# bits.net
KiCad netlist of a schematic drawn in EAGLE
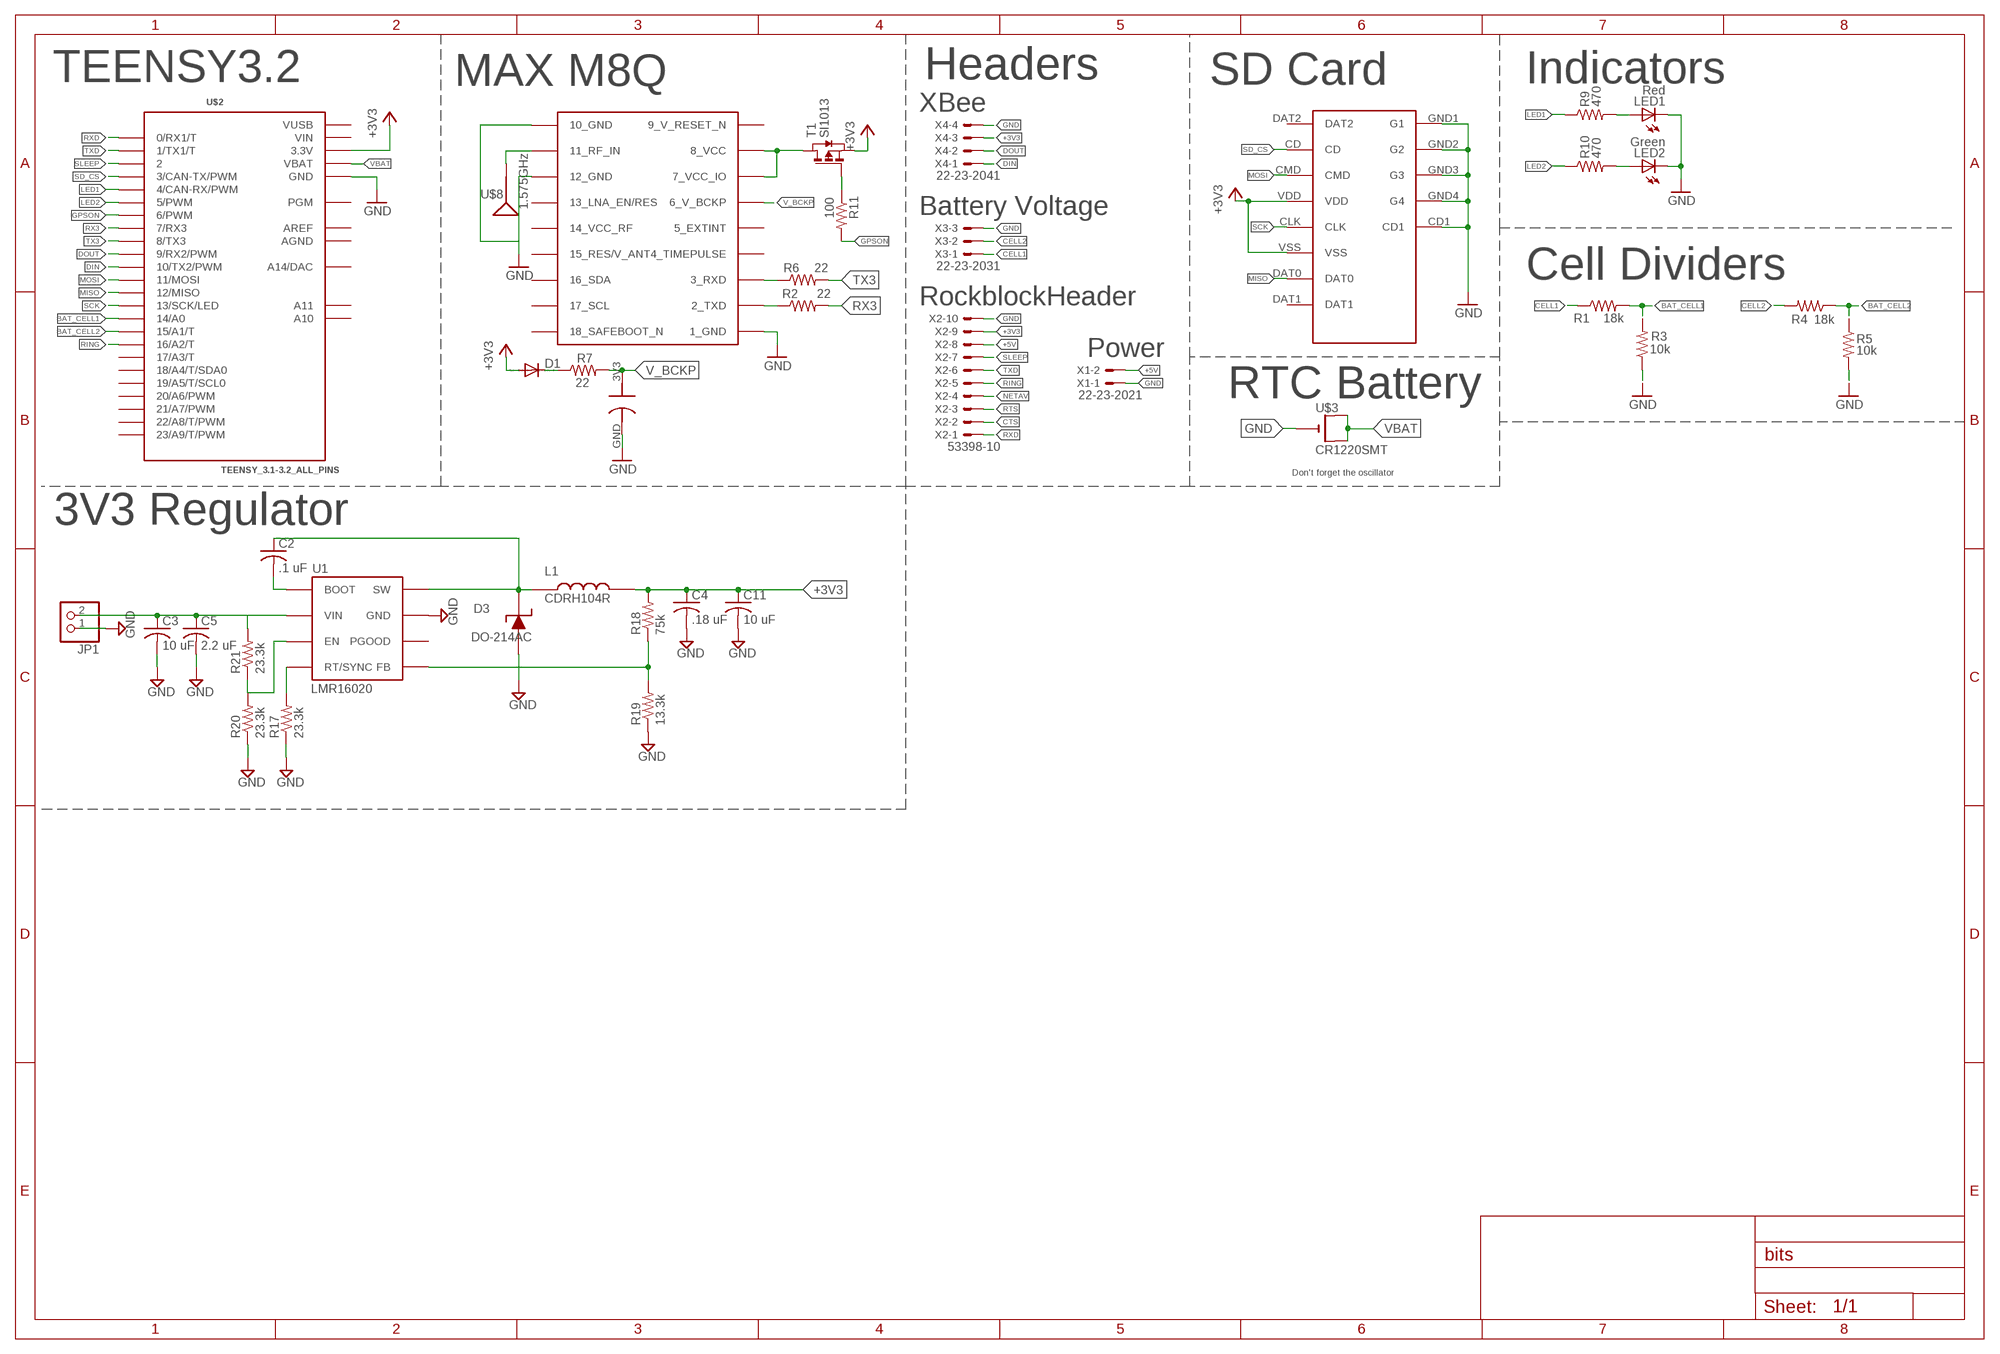
[diagram p0: schematic, sheet 1]

(export (version "E")
  (design (tool "Eeschema 10.0.6"))
  (components
    (comp (ref "C1")
      (value "DCK-3R3E204T614-E")
      (footprint "eagle-import:ELNASUPERCAP")
      (libsource (lib "eagle-import") (part "DCK-3R3E204T614-E"))
    )
    (comp (ref "C2")
      (value ".1 uF")
      (footprint "eagle-import:C0603")
      (libsource (lib "eagle-import") (part "C-USC0603"))
    )
    (comp (ref "C3")
      (value "10 uF")
      (footprint "eagle-import:C1210")
      (libsource (lib "eagle-import") (part "C-USC1210"))
    )
    (comp (ref "C4")
      (value ".18 uF")
      (footprint "eagle-import:C0603")
      (libsource (lib "eagle-import") (part "C-USC0603"))
    )
    (comp (ref "C5")
      (value "2.2 uF")
      (footprint "eagle-import:C1210")
      (libsource (lib "eagle-import") (part "C-USC1210"))
    )
    (comp (ref "C11")
      (value "10 uF")
      (footprint "eagle-import:C0603")
      (libsource (lib "eagle-import") (part "C-USC0603"))
    )
    (comp (ref "D1")
      (value "DIODE-SOD523")
      (footprint "eagle-import:SOD523")
      (libsource (lib "eagle-import") (part "DIODE-SOD523"))
    )
    (comp (ref "D3")
      (value "DO-214AC")
      (footprint "eagle-import:DO-214AC")
      (libsource (lib "eagle-import") (part "DO-214AC"))
    )
    (comp (ref "JP1")
      (value "PINHD-1X2")
      (footprint "eagle-import:1X02")
      (libsource (lib "eagle-import") (part "PINHD-1X2"))
    )
    (comp (ref "L1")
      (value "CDRH104R")
      (footprint "eagle-import:CDRH104R")
      (libsource (lib "eagle-import") (part "CDRH104R"))
    )
    (comp (ref "LED1")
      (value "Red")
      (footprint "eagle-import:CHIP-LED0603")
      (libsource (lib "eagle-import") (part "LEDCHIP-LED0603"))
    )
    (comp (ref "LED2")
      (value "Green")
      (footprint "eagle-import:CHIP-LED0603")
      (libsource (lib "eagle-import") (part "LEDCHIP-LED0603"))
    )
    (comp (ref "R1")
      (value "18k")
      (footprint "eagle-import:R0603")
      (libsource (lib "eagle-import") (part "resistor_R-US_R0603"))
    )
    (comp (ref "R2")
      (value "22")
      (footprint "eagle-import:R0603")
      (libsource (lib "eagle-import") (part "R-US_R0603"))
    )
    (comp (ref "R3")
      (value "10k")
      (footprint "eagle-import:R0603")
      (libsource (lib "eagle-import") (part "resistor_R-US_R0603"))
    )
    (comp (ref "R4")
      (value "18k")
      (footprint "eagle-import:R0603")
      (libsource (lib "eagle-import") (part "resistor_R-US_R0603"))
    )
    (comp (ref "R5")
      (value "10k")
      (footprint "eagle-import:R0603")
      (libsource (lib "eagle-import") (part "resistor_R-US_R0603"))
    )
    (comp (ref "R6")
      (value "22")
      (footprint "eagle-import:R0603")
      (libsource (lib "eagle-import") (part "R-US_R0603"))
    )
    (comp (ref "R7")
      (value "22")
      (footprint "eagle-import:R0603")
      (libsource (lib "eagle-import") (part "R-US_R0603"))
    )
    (comp (ref "R9")
      (value "470")
      (footprint "eagle-import:R0603")
      (libsource (lib "eagle-import") (part "resistor_R-US_R0603"))
    )
    (comp (ref "R10")
      (value "470")
      (footprint "eagle-import:R0603")
      (libsource (lib "eagle-import") (part "resistor_R-US_R0603"))
    )
    (comp (ref "R11")
      (value "100")
      (footprint "eagle-import:R0603")
      (libsource (lib "eagle-import") (part "R-US_R0603"))
    )
    (comp (ref "R17")
      (value "23.3k")
      (footprint "eagle-import:R0603")
      (libsource (lib "eagle-import") (part "resistor_R-US_R0603"))
    )
    (comp (ref "R18")
      (value "75k")
      (footprint "eagle-import:R0603")
      (libsource (lib "eagle-import") (part "resistor_R-US_R0603"))
    )
    (comp (ref "R19")
      (value "13.3k")
      (footprint "eagle-import:R0603")
      (libsource (lib "eagle-import") (part "resistor_R-US_R0603"))
    )
    (comp (ref "R20")
      (value "23.3k")
      (footprint "eagle-import:R0603")
      (libsource (lib "eagle-import") (part "resistor_R-US_R0603"))
    )
    (comp (ref "R21")
      (value "23.3k")
      (footprint "eagle-import:R0603")
      (libsource (lib "eagle-import") (part "resistor_R-US_R0603"))
    )
    (comp (ref "T1")
      (value "SI1013")
      (footprint "eagle-import:SC-75")
      (libsource (lib "eagle-import") (part "SI1013"))
    )
    (comp (ref "U$2")
      (value "TEENSY_3.1-3.2_ALL_PINS")
      (footprint "eagle-import:TEENSY_3.0-3.2&LC_ALL_PINS")
      (libsource (lib "eagle-import") (part "TEENSY_3.1-3.2_ALL_PINS"))
    )
    (comp (ref "U$3")
      (value "CR1220SMT")
      (footprint "eagle-import:CR1220-SMD")
      (libsource (lib "eagle-import") (part "CR1220SMT"))
    )
    (comp (ref "U$4")
      (value "MICRO_SD")
      (footprint "eagle-import:MICRO_SD_HINGED")
      (libsource (lib "eagle-import") (part "MICRO_SD"))
    )
    (comp (ref "U$7")
      (value "MAX-M8")
      (footprint "eagle-import:MAX-M8")
      (libsource (lib "eagle-import") (part "MAX-M8"))
    )
    (comp (ref "U$8")
      (value "1.575GHz")
      (footprint "eagle-import:SPARKFUN-GPS_ANT-GPS-2X7MM")
      (libsource (lib "eagle-import") (part "SPARKFUN-GPS_ANTENNAGPS-2X7MM"))
    )
    (comp (ref "U1")
      (value "LMR16020")
      (footprint "eagle-import:SO8")
      (libsource (lib "eagle-import") (part "LMR16020"))
    )
    (comp (ref "X1")
      (value "22-23-2021")
      (footprint "eagle-import:22-23-2021")
      (fields (field (name "MF") "MOLEX"))
      (libsource (lib "eagle-import") (part "22-23-2021"))
    )
    (comp (ref "X2")
      (value "53398-10")
      (footprint "eagle-import:53398-10")
      (fields (field (name "MF") "MOLEX") (field (name "MPN") "53398-1071"))
      (libsource (lib "eagle-import") (part "53?-10398"))
    )
    (comp (ref "X3")
      (value "22-23-2031")
      (footprint "eagle-import:22-23-2031")
      (fields (field (name "MF") "MOLEX"))
      (libsource (lib "eagle-import") (part "22-23-2031"))
    )
    (comp (ref "X4")
      (value "22-23-2041")
      (footprint "eagle-import:22-23-2041")
      (fields (field (name "MF") "MOLEX"))
      (libsource (lib "eagle-import") (part "22-23-2041"))
    )
  )
  (nets
    (net (code "1") (name "+3V3") (class "Default")
      (node (ref "C11") (pin "1") (pinfunction "1_1") (pintype "passive"))
      (node (ref "C4") (pin "1") (pinfunction "1_1") (pintype "passive"))
      (node (ref "D1") (pin "A") (pinfunction "A_A") (pintype "passive"))
      (node (ref "L1") (pin "P$2") (pinfunction "P$2_P$2") (pintype "bidirectional"))
      (node (ref "R18") (pin "2") (pinfunction "2_2") (pintype "passive"))
      (node (ref "T1") (pin "P$2") (pinfunction "S_P$2") (pintype "passive"))
      (node (ref "U$2") (pin "3.3V") (pinfunction "3.3V_3.3V") (pintype "power_in"))
      (node (ref "U$2") (pin "3.3V1") (pinfunction "3.3V_3.3V1") (pintype "power_in"))
      (node (ref "U$4") (pin "VDD") (pinfunction "VDD_VDD") (pintype "bidirectional"))
      (node (ref "U$4") (pin "VSS") (pinfunction "VSS_VSS") (pintype "bidirectional"))
      (node (ref "X2") (pin "9") (pinfunction "S_9") (pintype "passive"))
      (node (ref "X4") (pin "3") (pinfunction "S_3") (pintype "passive"))
    )
    (net (code "2") (name "+5V") (class "Default")
      (node (ref "X1") (pin "2") (pinfunction "S_2") (pintype "passive"))
      (node (ref "X2") (pin "8") (pinfunction "S_8") (pintype "passive"))
    )
    (net (code "3") (name "/9_V_RESET_N") (class "Default")
      (node (ref "U$7") (pin "9_RESET_N") (pinfunction "9_V_RESET_N_9_RESET_N") (pintype "power_in"))
    )
    (net (code "4") (name "/AGND") (class "Default")
      (node (ref "U$2") (pin "AGND") (pinfunction "AGND_AGND") (pintype "power_in"))
    )
    (net (code "5") (name "/AREF") (class "Default")
      (node (ref "U$2") (pin "AREF") (pinfunction "AREF_AREF") (pintype "power_in"))
    )
    (net (code "6") (name "/VIN") (class "Default")
      (node (ref "U$2") (pin "VIN") (pinfunction "VIN_VIN") (pintype "power_in"))
    )
    (net (code "7") (name "/VUSB") (class "Default")
      (node (ref "U$2") (pin "VUSB") (pinfunction "VUSB_VUSB") (pintype "power_in"))
    )
    (net (code "8") (name "BAT_CELL1") (class "Default")
      (node (ref "R1") (pin "2") (pinfunction "2_2") (pintype "passive"))
      (node (ref "R3") (pin "2") (pinfunction "2_2") (pintype "passive"))
      (node (ref "U$2") (pin "14/A0") (pinfunction "14/A0_14/A0") (pintype "bidirectional"))
    )
    (net (code "9") (name "BAT_CELL2") (class "Default")
      (node (ref "R4") (pin "1") (pinfunction "1_1") (pintype "passive"))
      (node (ref "R5") (pin "1") (pinfunction "1_1") (pintype "passive"))
      (node (ref "U$2") (pin "15/A1") (pinfunction "15/A1/T_15/A1") (pintype "bidirectional"))
    )
    (net (code "10") (name "CELL1") (class "Default")
      (node (ref "R1") (pin "1") (pinfunction "1_1") (pintype "passive"))
      (node (ref "X3") (pin "1") (pinfunction "S_1") (pintype "passive"))
    )
    (net (code "11") (name "CELL2") (class "Default")
      (node (ref "R4") (pin "2") (pinfunction "2_2") (pintype "passive"))
      (node (ref "X3") (pin "2") (pinfunction "S_2") (pintype "passive"))
    )
    (net (code "12") (name "CTS") (class "Default")
      (node (ref "X2") (pin "2") (pinfunction "S_2") (pintype "passive"))
    )
    (net (code "13") (name "DIN") (class "Default")
      (node (ref "U$2") (pin "10") (pinfunction "10/TX2/PWM_10") (pintype "bidirectional"))
      (node (ref "X4") (pin "1") (pinfunction "S_1") (pintype "passive"))
    )
    (net (code "14") (name "DOUT") (class "Default")
      (node (ref "U$2") (pin "9") (pinfunction "9/RX2/PWM_9") (pintype "bidirectional"))
      (node (ref "X4") (pin "2") (pinfunction "S_2") (pintype "passive"))
    )
    (net (code "15") (name "GND") (class "Default")
      (node (ref "C1") (pin "GND") (pinfunction "GND_GND") (pintype "bidirectional"))
      (node (ref "C11") (pin "2") (pinfunction "2_2") (pintype "passive"))
      (node (ref "C3") (pin "2") (pinfunction "2_2") (pintype "passive"))
      (node (ref "C4") (pin "2") (pinfunction "2_2") (pintype "passive"))
      (node (ref "C5") (pin "2") (pinfunction "2_2") (pintype "passive"))
      (node (ref "D3") (pin "P$1") (pinfunction "P$1_P$1") (pintype "bidirectional"))
      (node (ref "JP1") (pin "1") (pinfunction "1_1") (pintype "passive"))
      (node (ref "LED1") (pin "C") (pinfunction "C_C") (pintype "passive"))
      (node (ref "LED2") (pin "C") (pinfunction "C_C") (pintype "passive"))
      (node (ref "R17") (pin "1") (pinfunction "1_1") (pintype "passive"))
      (node (ref "R19") (pin "1") (pinfunction "1_1") (pintype "passive"))
      (node (ref "R20") (pin "1") (pinfunction "1_1") (pintype "passive"))
      (node (ref "R3") (pin "1") (pinfunction "1_1") (pintype "passive"))
      (node (ref "R5") (pin "2") (pinfunction "2_2") (pintype "passive"))
      (node (ref "U$2") (pin "GND") (pinfunction "GND_GND") (pintype "power_in"))
      (node (ref "U$2") (pin "GND1") (pinfunction "GND_GND1") (pintype "power_in"))
      (node (ref "U$3") (pin "-") (pinfunction "-_-") (pintype "passive"))
      (node (ref "U$4") (pin "CD1") (pinfunction "CD1_CD1") (pintype "bidirectional"))
      (node (ref "U$4") (pin "GND1") (pinfunction "G1_GND1") (pintype "bidirectional"))
      (node (ref "U$4") (pin "GND2") (pinfunction "G2_GND2") (pintype "bidirectional"))
      (node (ref "U$4") (pin "GND3") (pinfunction "G3_GND3") (pintype "bidirectional"))
      (node (ref "U$4") (pin "GND4") (pinfunction "G4_GND4") (pintype "bidirectional"))
      (node (ref "U$7") (pin "10_GND") (pinfunction "10_GND_10_GND") (pintype "power_in"))
      (node (ref "U$7") (pin "12_GND") (pinfunction "12_GND_12_GND") (pintype "power_in"))
      (node (ref "U$7") (pin "1_GND") (pinfunction "1_GND_1_GND") (pintype "power_in"))
      (node (ref "U1") (pin "P$7") (pinfunction "GND_P$7") (pintype "bidirectional"))
      (node (ref "U1") (pin "PAD") (pinfunction "GND_PAD") (pintype "bidirectional"))
      (node (ref "X1") (pin "1") (pinfunction "S_1") (pintype "passive"))
      (node (ref "X2") (pin "10") (pinfunction "S_10") (pintype "passive"))
      (node (ref "X3") (pin "3") (pinfunction "S_3") (pintype "passive"))
      (node (ref "X4") (pin "4") (pinfunction "S_4") (pintype "passive"))
    )
    (net (code "16") (name "GPSON") (class "Default")
      (node (ref "R11") (pin "2") (pinfunction "2_2") (pintype "passive"))
      (node (ref "U$2") (pin "6") (pinfunction "6/PWM_6") (pintype "bidirectional"))
    )
    (net (code "17") (name "LED1") (class "Default")
      (node (ref "R9") (pin "1") (pinfunction "1_1") (pintype "passive"))
      (node (ref "U$2") (pin "4") (pinfunction "4/CAN-RX/PWM_4") (pintype "bidirectional"))
    )
    (net (code "18") (name "LED2") (class "Default")
      (node (ref "R10") (pin "1") (pinfunction "1_1") (pintype "passive"))
      (node (ref "U$2") (pin "5") (pinfunction "5/PWM_5") (pintype "bidirectional"))
    )
    (net (code "19") (name "MISO") (class "Default")
      (node (ref "U$2") (pin "12") (pinfunction "12/MISO_12") (pintype "bidirectional"))
      (node (ref "U$4") (pin "DAT0") (pinfunction "DAT0_DAT0") (pintype "bidirectional"))
    )
    (net (code "20") (name "MOSI") (class "Default")
      (node (ref "U$2") (pin "11") (pinfunction "11/MOSI_11") (pintype "bidirectional"))
      (node (ref "U$4") (pin "CMD") (pinfunction "CMD_CMD") (pintype "bidirectional"))
    )
    (net (code "21") (name "NETAV") (class "Default")
      (node (ref "X2") (pin "4") (pinfunction "S_4") (pintype "passive"))
    )
    (net (code "22") (name "Net-(D1-PadC)") (class "Default")
      (node (ref "D1") (pin "C") (pinfunction "C_C") (pintype "passive"))
      (node (ref "R7") (pin "1") (pinfunction "1_1") (pintype "passive"))
    )
    (net (code "23") (name "Net-(LED1-PadA)") (class "Default")
      (node (ref "LED1") (pin "A") (pinfunction "A_A") (pintype "passive"))
      (node (ref "R9") (pin "2") (pinfunction "2_2") (pintype "passive"))
    )
    (net (code "24") (name "Net-(LED2-PadA)") (class "Default")
      (node (ref "LED2") (pin "A") (pinfunction "A_A") (pintype "passive"))
      (node (ref "R10") (pin "2") (pinfunction "2_2") (pintype "passive"))
    )
    (net (code "25") (name "Net-(R2-Pad1)") (class "Default")
      (node (ref "R2") (pin "1") (pinfunction "1_1") (pintype "passive"))
      (node (ref "U$7") (pin "2_TXD") (pinfunction "2_TXD_2_TXD") (pintype "bidirectional"))
    )
    (net (code "26") (name "Net-(R6-Pad1)") (class "Default")
      (node (ref "R6") (pin "1") (pinfunction "1_1") (pintype "passive"))
      (node (ref "U$7") (pin "3_RXD") (pinfunction "3_RXD_3_RXD") (pintype "bidirectional"))
    )
    (net (code "27") (name "Net-(T1-D)") (class "Default")
      (node (ref "T1") (pin "P$3") (pinfunction "D_P$3") (pintype "passive"))
      (node (ref "U$7") (pin "7_VCC_IO") (pinfunction "7_VCC_IO_7_VCC_IO") (pintype "power_in"))
      (node (ref "U$7") (pin "8_VCC") (pinfunction "8_VCC_8_VCC") (pintype "power_in"))
    )
    (net (code "28") (name "Net-(T1-G)") (class "Default")
      (node (ref "R11") (pin "1") (pinfunction "1_1") (pintype "passive"))
      (node (ref "T1") (pin "P$1") (pinfunction "G_P$1") (pintype "passive"))
    )
    (net (code "29") (name "Net-(U$8-SIGNAL)") (class "Default")
      (node (ref "U$7") (pin "11_RF_IN") (pinfunction "11_RF_IN_11_RF_IN") (pintype "bidirectional"))
      (node (ref "U$8") (pin "1") (pinfunction "SIGNAL_1") (pintype "bidirectional"))
    )
    (net (code "30") (name "Net-(U1-BOOT)") (class "Default")
      (node (ref "C2") (pin "2") (pinfunction "2_2") (pintype "passive"))
      (node (ref "U1") (pin "P$1") (pinfunction "BOOT_P$1") (pintype "bidirectional"))
    )
    (net (code "31") (name "Net-(U1-EN)") (class "Default")
      (node (ref "R20") (pin "2") (pinfunction "2_2") (pintype "passive"))
      (node (ref "R21") (pin "1") (pinfunction "1_1") (pintype "passive"))
      (node (ref "U1") (pin "P$3") (pinfunction "EN_P$3") (pintype "bidirectional"))
    )
    (net (code "32") (name "Net-(U1-FB)") (class "Default")
      (node (ref "R18") (pin "1") (pinfunction "1_1") (pintype "passive"))
      (node (ref "R19") (pin "2") (pinfunction "2_2") (pintype "passive"))
      (node (ref "U1") (pin "P$5") (pinfunction "FB_P$5") (pintype "bidirectional"))
    )
    (net (code "33") (name "Net-(U1-RT{slash}SYNC)") (class "Default")
      (node (ref "R17") (pin "2") (pinfunction "2_2") (pintype "passive"))
      (node (ref "U1") (pin "P$4") (pinfunction "RT/SYNC_P$4") (pintype "bidirectional"))
    )
    (net (code "34") (name "Net-(U1-SW)") (class "Default")
      (node (ref "C2") (pin "1") (pinfunction "1_1") (pintype "passive"))
      (node (ref "D3") (pin "P$2") (pinfunction "P$2_P$2") (pintype "bidirectional"))
      (node (ref "L1") (pin "P$1") (pinfunction "P$1_P$1") (pintype "bidirectional"))
      (node (ref "U1") (pin "P$8") (pinfunction "SW_P$8") (pintype "bidirectional"))
    )
    (net (code "35") (name "Net-(U1-VIN)") (class "Default")
      (node (ref "C3") (pin "1") (pinfunction "1_1") (pintype "passive"))
      (node (ref "C5") (pin "1") (pinfunction "1_1") (pintype "passive"))
      (node (ref "JP1") (pin "2") (pinfunction "2_2") (pintype "passive"))
      (node (ref "R21") (pin "2") (pinfunction "2_2") (pintype "passive"))
      (node (ref "U1") (pin "P$2") (pinfunction "VIN_P$2") (pintype "bidirectional"))
    )
    (net (code "36") (name "RING") (class "Default")
      (node (ref "U$2") (pin "16/A2") (pinfunction "16/A2/T_16/A2") (pintype "bidirectional"))
      (node (ref "X2") (pin "5") (pinfunction "S_5") (pintype "passive"))
    )
    (net (code "37") (name "RTS") (class "Default")
      (node (ref "X2") (pin "3") (pinfunction "S_3") (pintype "passive"))
    )
    (net (code "38") (name "RX3") (class "Default")
      (node (ref "R2") (pin "2") (pinfunction "2_2") (pintype "passive"))
      (node (ref "U$2") (pin "7") (pinfunction "7/RX3_7") (pintype "bidirectional"))
    )
    (net (code "39") (name "RXD") (class "Default")
      (node (ref "U$2") (pin "0") (pinfunction "0/RX1/T_0") (pintype "bidirectional"))
      (node (ref "X2") (pin "1") (pinfunction "S_1") (pintype "passive"))
    )
    (net (code "40") (name "SCK") (class "Default")
      (node (ref "U$2") (pin "13") (pinfunction "13/SCK/LED_13") (pintype "bidirectional"))
      (node (ref "U$4") (pin "CLK") (pinfunction "CLK_CLK") (pintype "bidirectional"))
    )
    (net (code "41") (name "SD_CS") (class "Default")
      (node (ref "U$2") (pin "3") (pinfunction "3/CAN-TX/PWM_3") (pintype "bidirectional"))
      (node (ref "U$4") (pin "CD") (pinfunction "CD_CD") (pintype "bidirectional"))
    )
    (net (code "42") (name "SLEEP") (class "Default")
      (node (ref "U$2") (pin "2") (pinfunction "2_2") (pintype "bidirectional"))
      (node (ref "X2") (pin "7") (pinfunction "S_7") (pintype "passive"))
    )
    (net (code "43") (name "TX3") (class "Default")
      (node (ref "R6") (pin "2") (pinfunction "2_2") (pintype "passive"))
      (node (ref "U$2") (pin "8") (pinfunction "8/TX3_8") (pintype "bidirectional"))
    )
    (net (code "44") (name "TXD") (class "Default")
      (node (ref "U$2") (pin "1") (pinfunction "1/TX1/T_1") (pintype "bidirectional"))
      (node (ref "X2") (pin "6") (pinfunction "S_6") (pintype "passive"))
    )
    (net (code "45") (name "VBAT") (class "Default")
      (node (ref "U$2") (pin "VBAT") (pinfunction "VBAT_VBAT") (pintype "power_in"))
      (node (ref "U$3") (pin "+$1") (pinfunction "+_+$1") (pintype "passive"))
      (node (ref "U$3") (pin "+$2") (pinfunction "+1_+$2") (pintype "passive"))
    )
    (net (code "46") (name "V_BCKP") (class "Default")
      (node (ref "C1") (pin "3V3") (pinfunction "3V3_3V3") (pintype "bidirectional"))
      (node (ref "R7") (pin "2") (pinfunction "2_2") (pintype "passive"))
      (node (ref "U$7") (pin "6_V_BCKP") (pinfunction "6_V_BCKP_6_V_BCKP") (pintype "bidirectional"))
    )
    (net (code "47") (name "unconnected-(U$2-17{slash}A3{slash}T-Pad17{slash}A3)") (class "Default")
      (node (ref "U$2") (pin "17/A3") (pinfunction "17/A3/T_17/A3") (pintype "bidirectional"))
    )
    (net (code "48") (name "unconnected-(U$2-18{slash}A4{slash}T{slash}SDA0-Pad18{slash}A4)") (class "Default")
      (node (ref "U$2") (pin "18/A4") (pinfunction "18/A4/T/SDA0_18/A4") (pintype "bidirectional"))
    )
    (net (code "49") (name "unconnected-(U$2-19{slash}A5{slash}T{slash}SCL0-Pad19{slash}A5)") (class "Default")
      (node (ref "U$2") (pin "19/A5") (pinfunction "19/A5/T/SCL0_19/A5") (pintype "bidirectional"))
    )
    (net (code "50") (name "unconnected-(U$2-20{slash}A6{slash}PWM-Pad20{slash}A6)") (class "Default")
      (node (ref "U$2") (pin "20/A6") (pinfunction "20/A6/PWM_20/A6") (pintype "bidirectional"))
    )
    (net (code "51") (name "unconnected-(U$2-21{slash}A7{slash}PWM-Pad21{slash}A7)") (class "Default")
      (node (ref "U$2") (pin "21/A7") (pinfunction "21/A7/PWM_21/A7") (pintype "bidirectional"))
    )
    (net (code "52") (name "unconnected-(U$2-22{slash}A8{slash}T{slash}PWM-Pad22{slash}A8)") (class "Default")
      (node (ref "U$2") (pin "22/A8") (pinfunction "22/A8/T/PWM_22/A8") (pintype "bidirectional"))
    )
    (net (code "53") (name "unconnected-(U$2-23{slash}A9{slash}T{slash}PWM-Pad23{slash}A9)") (class "Default")
      (node (ref "U$2") (pin "23/A9") (pinfunction "23/A9/T/PWM_23/A9") (pintype "bidirectional"))
    )
    (net (code "54") (name "unconnected-(U$2-A14{slash}DAC-PadRESET{slash}DAC)") (class "Default")
      (node (ref "U$2") (pin "RESET/DAC") (pinfunction "A14/DAC_RESET/DAC") (pintype "bidirectional"))
    )
    (net (code "55") (name "unconnected-(U$2-PadA10)") (class "Default")
      (node (ref "U$2") (pin "A10") (pinfunction "A10_A10") (pintype "bidirectional"))
    )
    (net (code "56") (name "unconnected-(U$2-PadA11)") (class "Default")
      (node (ref "U$2") (pin "A11") (pinfunction "A11_A11") (pintype "bidirectional"))
    )
    (net (code "57") (name "unconnected-(U$2-PadPGM)") (class "Default")
      (node (ref "U$2") (pin "PGM") (pinfunction "PGM_PGM") (pintype "bidirectional"))
    )
    (net (code "58") (name "unconnected-(U$4-PadDAT1)") (class "Default")
      (node (ref "U$4") (pin "DAT1") (pinfunction "DAT1_DAT1") (pintype "bidirectional"))
    )
    (net (code "59") (name "unconnected-(U$4-PadDAT2)") (class "Default")
      (node (ref "U$4") (pin "DAT2") (pinfunction "DAT2_DAT2") (pintype "bidirectional"))
    )
    (net (code "60") (name "unconnected-(U$7-13_LNA_EN{slash}RES-Pad13_LNA_EN)") (class "Default")
      (node (ref "U$7") (pin "13_LNA_EN") (pinfunction "13_LNA_EN/RES_13_LNA_EN") (pintype "bidirectional"))
    )
    (net (code "61") (name "unconnected-(U$7-15_RES{slash}V_ANT-Pad15_V_ANT{slash}RESERVED)") (class "Default")
      (node (ref "U$7") (pin "15_V_ANT/RESERVED") (pinfunction "15_RES/V_ANT_15_V_ANT/RESERVED") (pintype "bidirectional"))
    )
    (net (code "62") (name "unconnected-(U$7-Pad4_TIMEPULSE)") (class "Default")
      (node (ref "U$7") (pin "4_TIMEPULSE") (pinfunction "4_TIMEPULSE_4_TIMEPULSE") (pintype "bidirectional"))
    )
    (net (code "63") (name "unconnected-(U$7-Pad5_EXTINT)") (class "Default")
      (node (ref "U$7") (pin "5_EXTINT") (pinfunction "5_EXTINT_5_EXTINT") (pintype "bidirectional"))
    )
    (net (code "64") (name "unconnected-(U$7-Pad14_VCC_RF)") (class "Default")
      (node (ref "U$7") (pin "14_VCC_RF") (pinfunction "14_VCC_RF_14_VCC_RF") (pintype "bidirectional"))
    )
    (net (code "65") (name "unconnected-(U$7-Pad16_SDA)") (class "Default")
      (node (ref "U$7") (pin "16_SDA") (pinfunction "16_SDA_16_SDA") (pintype "bidirectional"))
    )
    (net (code "66") (name "unconnected-(U$7-Pad17_SCL)") (class "Default")
      (node (ref "U$7") (pin "17_SCL") (pinfunction "17_SCL_17_SCL") (pintype "bidirectional"))
    )
    (net (code "67") (name "unconnected-(U$7-Pad18_SAFEBOOT_N)") (class "Default")
      (node (ref "U$7") (pin "18_SAFEBOOT_N") (pinfunction "18_SAFEBOOT_N_18_SAFEBOOT_N") (pintype "bidirectional"))
    )
    (net (code "68") (name "unconnected-(U1-PGOOD-PadP$6)") (class "Default")
      (node (ref "U1") (pin "P$6") (pinfunction "PGOOD_P$6") (pintype "bidirectional"))
    )
  )
)
